# DC-DC_prom_v2.net
KiCad netlist of a schematic drawn in EAGLE
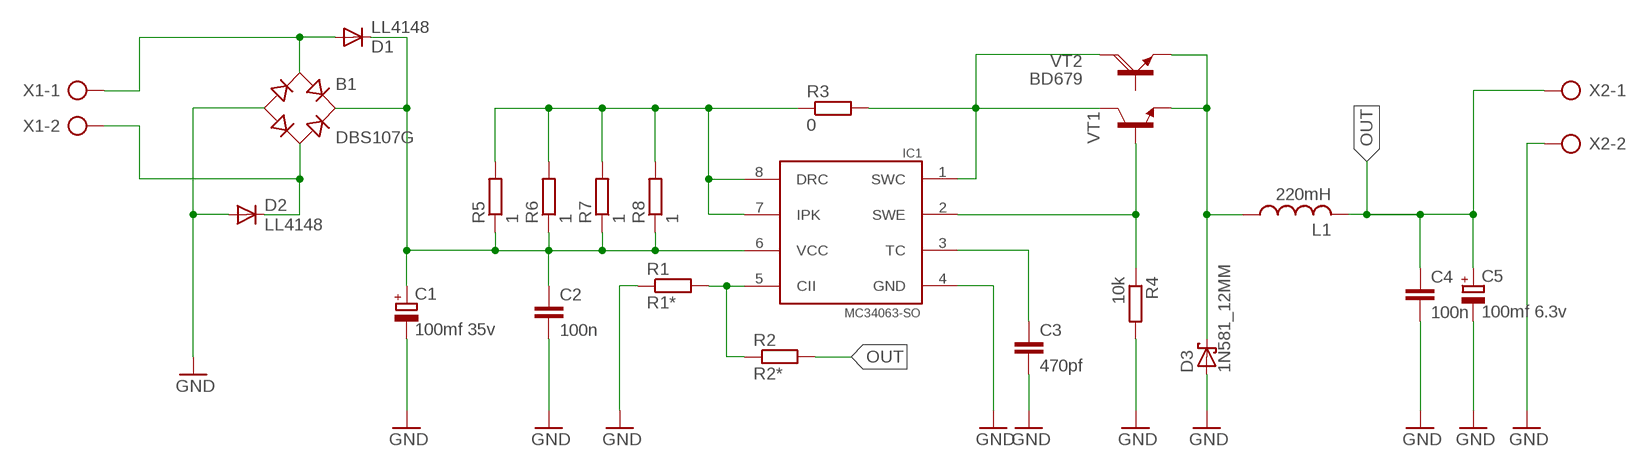
[diagram p0: schematic, sheet 1]

(export (version "E")
  (design (tool "Eeschema 10.0.6"))
  (components
    (comp (ref "B1")
      (value "DBS107G")
      (footprint "eagle-import:DBS")
      (libsource (lib "eagle-import") (part "DB?GS107"))
    )
    (comp (ref "C1")
      (value "100mf 35v")
      (footprint "eagle-import:E2,5-7")
      (libsource (lib "eagle-import") (part "CPOL-EUE2.5-7"))
    )
    (comp (ref "C2")
      (value "100n")
      (footprint "eagle-import:C0805")
      (libsource (lib "eagle-import") (part "C-EUC0805"))
    )
    (comp (ref "C3")
      (value "470pf")
      (footprint "eagle-import:C0805")
      (libsource (lib "eagle-import") (part "C-EUC0805"))
    )
    (comp (ref "C4")
      (value "100n")
      (footprint "eagle-import:C0805")
      (libsource (lib "eagle-import") (part "C-EUC0805"))
    )
    (comp (ref "C5")
      (value "100mf 6.3v")
      (footprint "eagle-import:E2,5-7")
      (libsource (lib "eagle-import") (part "CPOL-EUE2.5-7"))
    )
    (comp (ref "D1")
      (value "LL4148")
      (footprint "eagle-import:SOD80_DO213AA_MINIMELF")
      (libsource (lib "eagle-import") (part "LL4148"))
    )
    (comp (ref "D2")
      (value "LL4148")
      (footprint "eagle-import:SOD80_DO213AA_MINIMELF")
      (libsource (lib "eagle-import") (part "LL4148"))
    )
    (comp (ref "D3")
      (value "1N581_12MM")
      (footprint "eagle-import:DO41-12")
      (libsource (lib "eagle-import") (part "1N581_12MM"))
    )
    (comp (ref "IC1")
      (value "MC34063-SO")
      (footprint "eagle-import:SO8")
      (libsource (lib "eagle-import") (part "MC34063-SO"))
    )
    (comp (ref "L1")
      (value "220mH")
      (footprint "eagle-import:6000-XXXX-RC")
      (libsource (lib "eagle-import") (part "L-US6000-XXX-RC"))
    )
    (comp (ref "R1")
      (value "R1*")
      (footprint "eagle-import:M0805")
      (libsource (lib "eagle-import") (part "R-EU_M0805"))
    )
    (comp (ref "R2")
      (value "R2*")
      (footprint "eagle-import:M0805")
      (libsource (lib "eagle-import") (part "R-EU_M0805"))
    )
    (comp (ref "R3")
      (value "0")
      (footprint "eagle-import:M1406")
      (libsource (lib "eagle-import") (part "R-EU_M1406"))
    )
    (comp (ref "R4")
      (value "10k")
      (footprint "eagle-import:M0805")
      (libsource (lib "eagle-import") (part "R-EU_M0805"))
    )
    (comp (ref "R5")
      (value "1")
      (footprint "eagle-import:M1206")
      (libsource (lib "eagle-import") (part "R-EU_M1206"))
    )
    (comp (ref "R6")
      (value "1")
      (footprint "eagle-import:M1206")
      (libsource (lib "eagle-import") (part "R-EU_M1206"))
    )
    (comp (ref "R7")
      (value "1")
      (footprint "eagle-import:M1206")
      (libsource (lib "eagle-import") (part "R-EU_M1206"))
    )
    (comp (ref "R8")
      (value "1")
      (footprint "eagle-import:M1206")
      (libsource (lib "eagle-import") (part "R-EU_M1206"))
    )
    (comp (ref "VT1")
      (value "BCX56-16")
      (footprint "eagle-import:SOT89")
      (libsource (lib "eagle-import") (part "BCX56-16"))
    )
    (comp (ref "VT2")
      (value "BD679")
      (footprint "eagle-import:TO126AV")
      (libsource (lib "eagle-import") (part "BD679"))
    )
    (comp (ref "X1")
      (value "AK500/2")
      (footprint "eagle-import:AK500_2")
      (libsource (lib "eagle-import") (part "AK500/2"))
    )
    (comp (ref "X2")
      (value "AK500/2")
      (footprint "eagle-import:AK500_2")
      (libsource (lib "eagle-import") (part "AK500/2"))
    )
  )
  (nets
    (net (code "1") (name "GND") (class "Default")
      (node (ref "B1") (pin "-") (pinfunction "-_-") (pintype "passive"))
      (node (ref "C1") (pin "-") (pinfunction "-_-") (pintype "passive"))
      (node (ref "C2") (pin "2") (pinfunction "2_2") (pintype "passive"))
      (node (ref "C3") (pin "2") (pinfunction "2_2") (pintype "passive"))
      (node (ref "C4") (pin "2") (pinfunction "2_2") (pintype "passive"))
      (node (ref "C5") (pin "-") (pinfunction "-_-") (pintype "passive"))
      (node (ref "D2") (pin "A") (pinfunction "A_A") (pintype "passive"))
      (node (ref "D3") (pin "A") (pinfunction "A_A") (pintype "passive"))
      (node (ref "IC1") (pin "4") (pinfunction "GND_4") (pintype "power_in"))
      (node (ref "R1") (pin "1") (pinfunction "1_1") (pintype "passive"))
      (node (ref "R4") (pin "2") (pinfunction "2_2") (pintype "passive"))
      (node (ref "X2") (pin "2") (pinfunction "KL_2") (pintype "passive"))
    )
    (net (code "2") (name "Net-(D3-PadC)") (class "Default")
      (node (ref "D3") (pin "C") (pinfunction "C_C") (pintype "passive"))
      (node (ref "L1") (pin "1") (pinfunction "1_1") (pintype "passive"))
      (node (ref "VT1") (pin "E") (pinfunction "E_E") (pintype "passive"))
      (node (ref "VT2") (pin "E") (pinfunction "E_E") (pintype "passive"))
    )
    (net (code "3") (name "Net-(IC1-CII)") (class "Default")
      (node (ref "IC1") (pin "5") (pinfunction "CII_5") (pintype "bidirectional"))
      (node (ref "R1") (pin "2") (pinfunction "2_2") (pintype "passive"))
      (node (ref "R2") (pin "1") (pinfunction "1_1") (pintype "passive"))
    )
    (net (code "4") (name "Net-(IC1-DRC)") (class "Default")
      (node (ref "IC1") (pin "7") (pinfunction "IPK_7") (pintype "bidirectional"))
      (node (ref "IC1") (pin "8") (pinfunction "DRC_8") (pintype "bidirectional"))
      (node (ref "R3") (pin "1") (pinfunction "1_1") (pintype "passive"))
      (node (ref "R5") (pin "2") (pinfunction "2_2") (pintype "passive"))
      (node (ref "R6") (pin "2") (pinfunction "2_2") (pintype "passive"))
      (node (ref "R7") (pin "2") (pinfunction "2_2") (pintype "passive"))
      (node (ref "R8") (pin "2") (pinfunction "2_2") (pintype "passive"))
    )
    (net (code "5") (name "Net-(IC1-SWC)") (class "Default")
      (node (ref "IC1") (pin "1") (pinfunction "SWC_1") (pintype "bidirectional"))
      (node (ref "R3") (pin "2") (pinfunction "2_2") (pintype "passive"))
      (node (ref "VT1") (pin "C") (pinfunction "C_C") (pintype "passive"))
      (node (ref "VT2") (pin "C") (pinfunction "C_C") (pintype "passive"))
    )
    (net (code "6") (name "Net-(IC1-SWE)") (class "Default")
      (node (ref "IC1") (pin "2") (pinfunction "SWE_2") (pintype "bidirectional"))
      (node (ref "R4") (pin "1") (pinfunction "1_1") (pintype "passive"))
      (node (ref "VT1") (pin "B") (pinfunction "B_B") (pintype "passive"))
    )
    (net (code "7") (name "Net-(IC1-TC)") (class "Default")
      (node (ref "C3") (pin "1") (pinfunction "1_1") (pintype "passive"))
      (node (ref "IC1") (pin "3") (pinfunction "TC_3") (pintype "bidirectional"))
    )
    (net (code "8") (name "Net-(IC1-VCC)") (class "Default")
      (node (ref "B1") (pin "+") (pinfunction "+_+") (pintype "passive"))
      (node (ref "C1") (pin "+") (pinfunction "+_+") (pintype "passive"))
      (node (ref "C2") (pin "1") (pinfunction "1_1") (pintype "passive"))
      (node (ref "D1") (pin "C") (pinfunction "C_C") (pintype "passive"))
      (node (ref "IC1") (pin "6") (pinfunction "VCC_6") (pintype "bidirectional"))
      (node (ref "R5") (pin "1") (pinfunction "1_1") (pintype "passive"))
      (node (ref "R6") (pin "1") (pinfunction "1_1") (pintype "passive"))
      (node (ref "R7") (pin "1") (pinfunction "1_1") (pintype "passive"))
      (node (ref "R8") (pin "1") (pinfunction "1_1") (pintype "passive"))
    )
    (net (code "9") (name "Net-(X1A-KL)") (class "Default")
      (node (ref "B1") (pin "AC1") (pinfunction "AC1_AC1") (pintype "passive"))
      (node (ref "D1") (pin "A") (pinfunction "A_A") (pintype "passive"))
      (node (ref "X1") (pin "1") (pinfunction "KL_1") (pintype "passive"))
    )
    (net (code "10") (name "Net-(X1B-KL)") (class "Default")
      (node (ref "B1") (pin "AC2") (pinfunction "AC2_AC2") (pintype "passive"))
      (node (ref "D2") (pin "C") (pinfunction "C_C") (pintype "passive"))
      (node (ref "X1") (pin "2") (pinfunction "KL_2") (pintype "passive"))
    )
    (net (code "11") (name "OUT") (class "Default")
      (node (ref "C4") (pin "1") (pinfunction "1_1") (pintype "passive"))
      (node (ref "C5") (pin "+") (pinfunction "+_+") (pintype "passive"))
      (node (ref "L1") (pin "2") (pinfunction "2_2") (pintype "passive"))
      (node (ref "R2") (pin "2") (pinfunction "2_2") (pintype "passive"))
      (node (ref "X2") (pin "1") (pinfunction "KL_1") (pintype "passive"))
    )
    (net (code "12") (name "unconnected-(VT2-PadB)") (class "Default")
      (node (ref "VT2") (pin "B") (pinfunction "B_B") (pintype "passive"))
    )
  )
)
